# MCU_1.net
KiCad netlist of a schematic drawn in Altium Designer
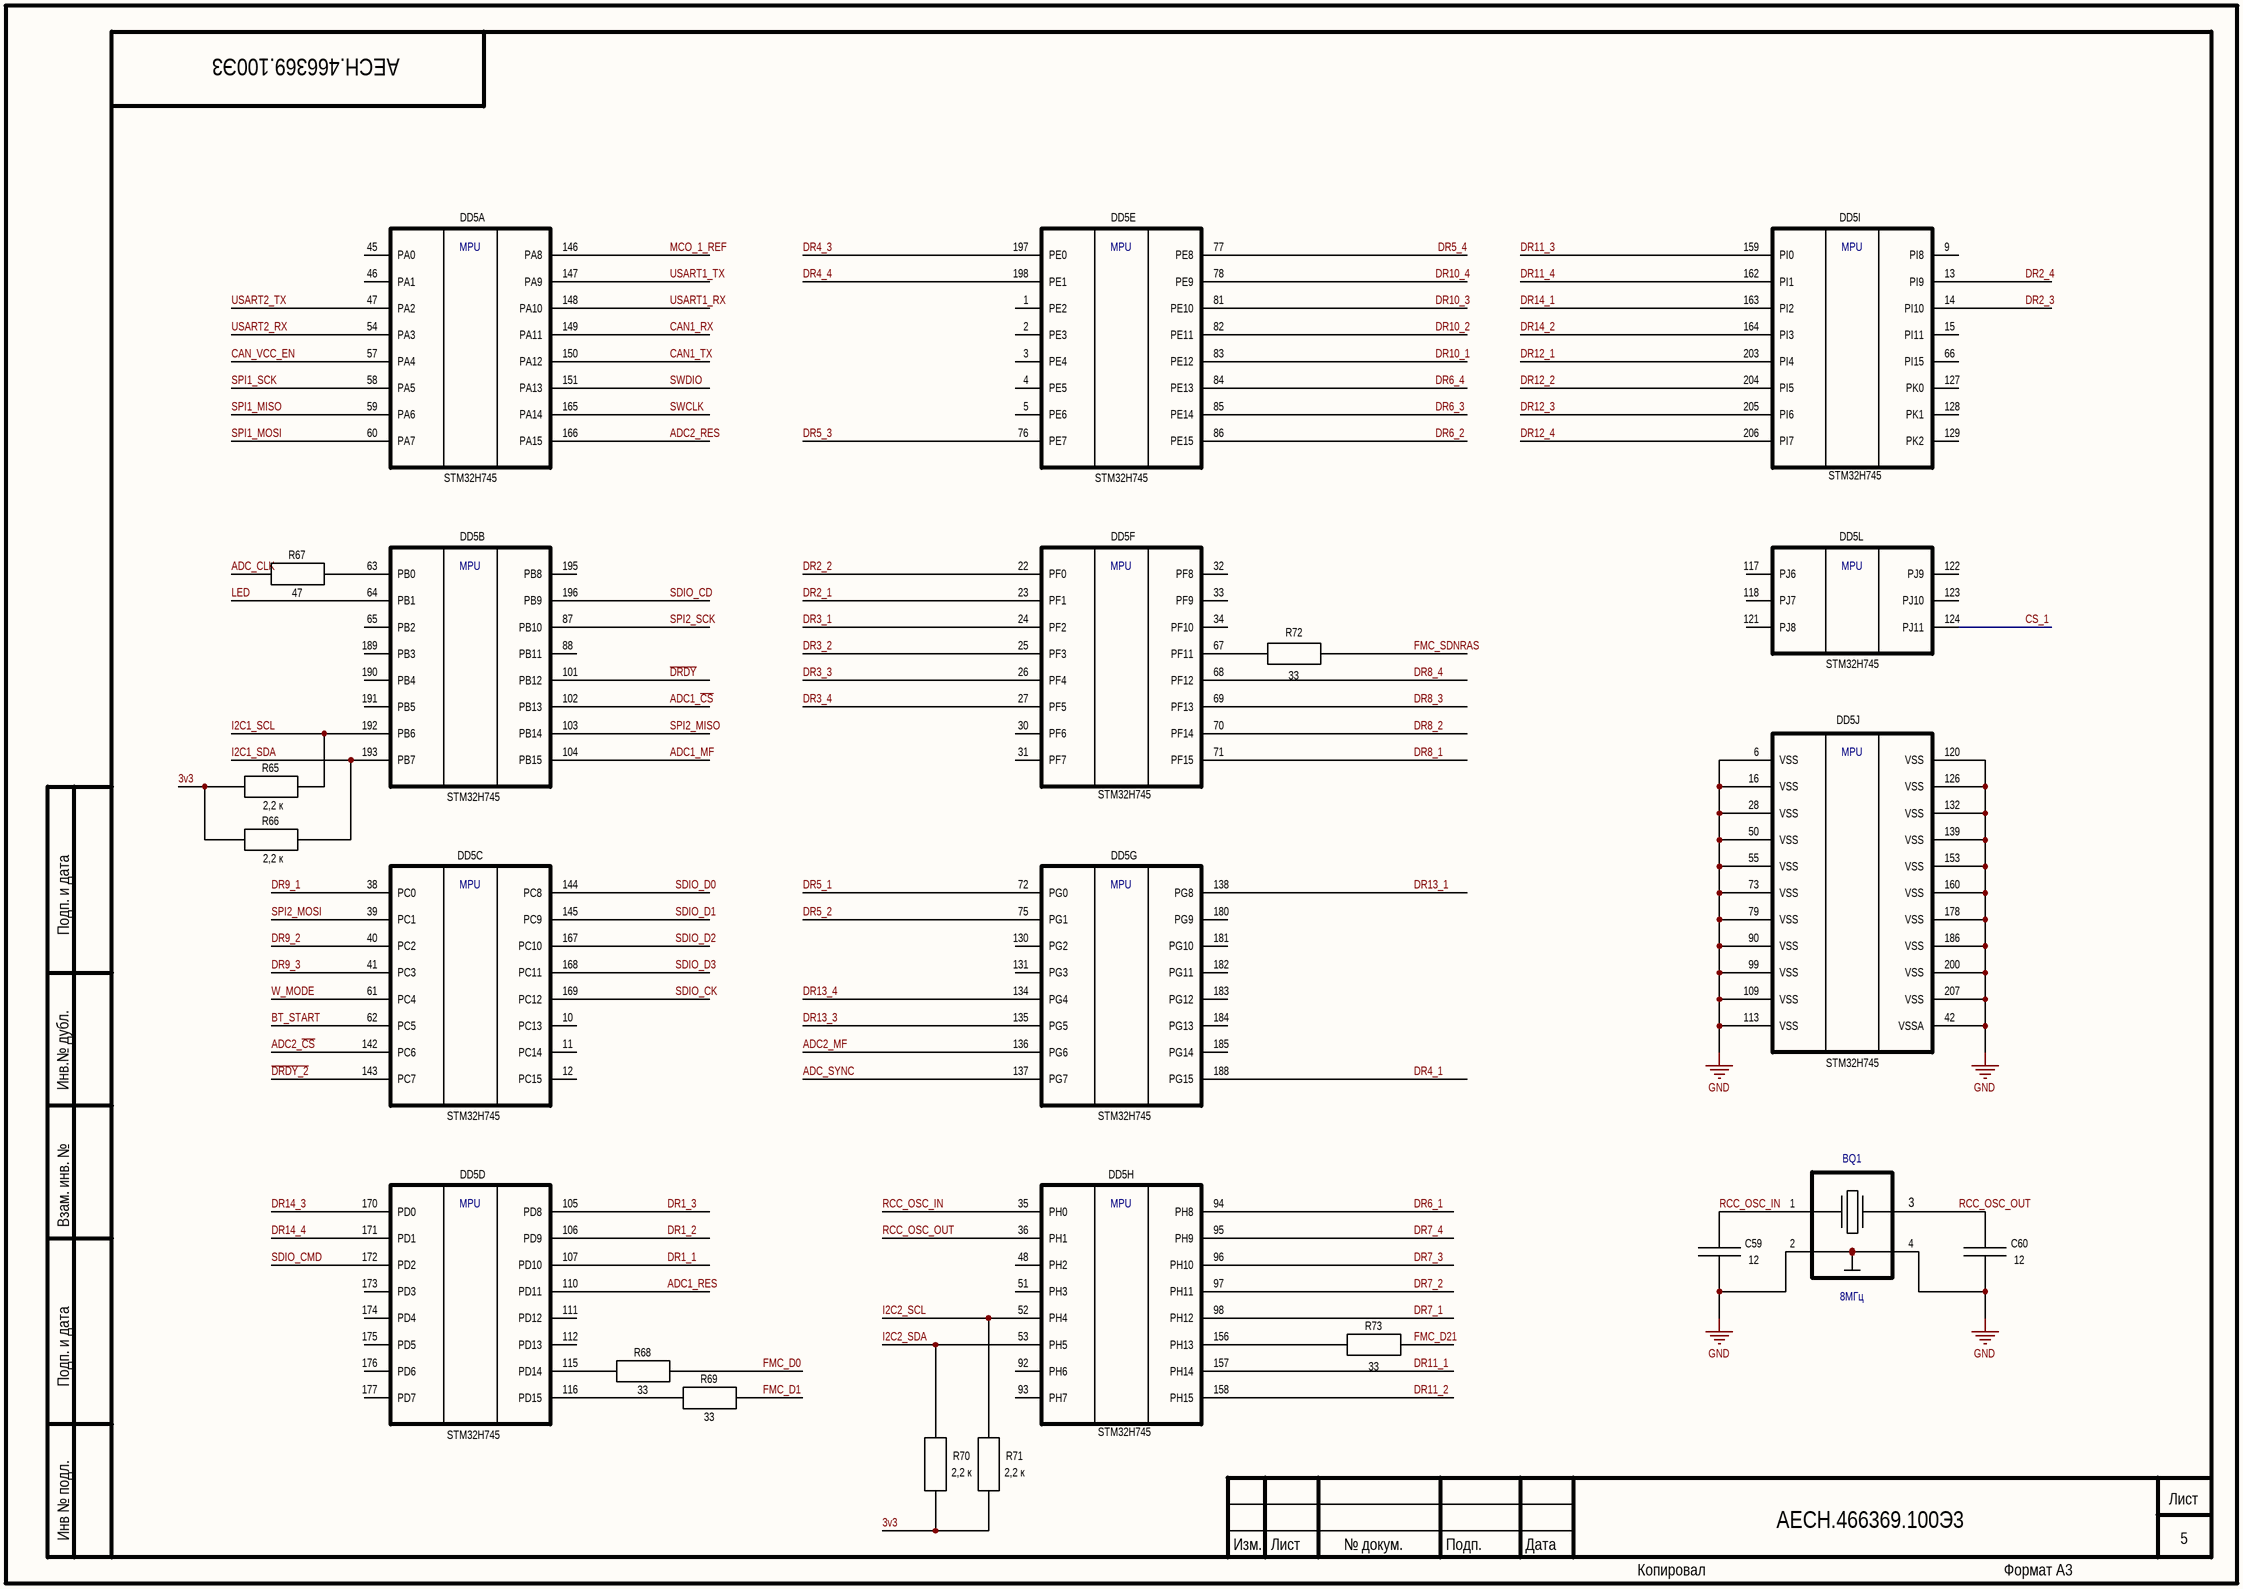
[diagram p0: MCU_1.SchDoc]

(export (version "E")
  (design (tool "Eeschema 10.0.6"))
  (components
    (comp (ref "BQ1")
      (value "8МГц")
      (footprint "Crystal_0532")
      (fields (field (name "PARTNUMBER") "KX-9AT 8.0 MHZ"))
      (libsource (lib "5ko") (part "OSC_4"))
    )
    (comp (ref "C59")
      (value "12")
      (footprint "C0603")
      (fields
        (field (name "TOLERANCE") "±10%")
        (field (name "VOLTAGE") "50 В")
        (field (name "PARTNUMBER") "GRM1885C1H120JA01J")
      )
      (libsource (lib "5ko") (part "C"))
    )
    (comp (ref "C60")
      (value "12")
      (footprint "C0603")
      (fields
        (field (name "TOLERANCE") "±10%")
        (field (name "VOLTAGE") "50 В")
        (field (name "PARTNUMBER") "GRM1885C1H120JA01J")
      )
      (libsource (lib "5ko") (part "C"))
    )
    (comp (ref "DD5") (value "STM32H745") (footprint "LQFP208") (libsource (lib "5ko") (part "STM32H745")))
    (comp (ref "R65")
      (value "2,2 к")
      (footprint "R0603")
      (fields
        (field (name "TOLERANCE") "±5%")
        (field (name "POWER") "0.1 Вт")
        (field (name "PARTNUMBER") "RC0603JR-072K2L")
      )
      (libsource (lib "5ko") (part "R"))
    )
    (comp (ref "R66")
      (value "2,2 к")
      (footprint "R0603")
      (fields
        (field (name "TOLERANCE") "±5%")
        (field (name "POWER") "0.1 Вт")
        (field (name "PARTNUMBER") "RC0603JR-072K2L")
      )
      (libsource (lib "5ko") (part "R"))
    )
    (comp (ref "R67")
      (value "47")
      (footprint "R0603")
      (fields
        (field (name "TOLERANCE") "±5%")
        (field (name "POWER") "0.1 Вт")
        (field (name "PARTNUMBER") "RC0603JR-0747RL")
      )
      (libsource (lib "5ko") (part "R"))
    )
    (comp (ref "R68")
      (value "33")
      (footprint "R0603")
      (fields
        (field (name "TOLERANCE") "±5%")
        (field (name "POWER") "0.1 Вт")
        (field (name "PARTNUMBER") "RC0603JR-0733RL")
      )
      (libsource (lib "5ko") (part "R"))
    )
    (comp (ref "R69")
      (value "33")
      (footprint "R0603")
      (fields
        (field (name "TOLERANCE") "±5%")
        (field (name "POWER") "0.1 Вт")
        (field (name "PARTNUMBER") "RC0603JR-0733RL")
      )
      (libsource (lib "5ko") (part "R"))
    )
    (comp (ref "R70")
      (value "2,2 к")
      (footprint "R0603")
      (fields
        (field (name "TOLERANCE") "±5%")
        (field (name "POWER") "0.1 Вт")
        (field (name "PARTNUMBER") "RC0603JR-072K2L")
      )
      (libsource (lib "5ko") (part "R"))
    )
    (comp (ref "R71")
      (value "2,2 к")
      (footprint "R0603")
      (fields
        (field (name "TOLERANCE") "±5%")
        (field (name "POWER") "0.1 Вт")
        (field (name "PARTNUMBER") "RC0603JR-072K2L")
      )
      (libsource (lib "5ko") (part "R"))
    )
    (comp (ref "R72")
      (value "33")
      (footprint "R0603")
      (fields
        (field (name "TOLERANCE") "±5%")
        (field (name "POWER") "0.1 Вт")
        (field (name "PARTNUMBER") "RC0603JR-0733RL")
      )
      (libsource (lib "5ko") (part "R"))
    )
    (comp (ref "R73")
      (value "33")
      (footprint "R0603")
      (fields
        (field (name "TOLERANCE") "±5%")
        (field (name "POWER") "0.1 Вт")
        (field (name "PARTNUMBER") "RC0603JR-0733RL")
      )
      (libsource (lib "5ko") (part "R"))
    )
  )
  (nets
    (net (code "1") (name "/3v3") (class "Default")
      (node (ref "R65") (pin "2") (pinfunction "2_2") (pintype "passive"))
      (node (ref "R66") (pin "2") (pinfunction "2_2") (pintype "passive"))
      (node (ref "R70") (pin "2") (pinfunction "2_2") (pintype "passive"))
      (node (ref "R71") (pin "2") (pinfunction "2_2") (pintype "passive"))
    )
    (net (code "2") (name "/ADC1_MF") (class "Default")
      (node (ref "DD5") (pin "104") (pinfunction "PB15_104") (pintype "passive"))
    )
    (net (code "3") (name "/ADC1_RES") (class "Default")
      (node (ref "DD5") (pin "110") (pinfunction "PD11_110") (pintype "passive"))
    )
    (net (code "4") (name "/ADC1_~{CS}") (class "Default")
      (node (ref "DD5") (pin "102") (pinfunction "PB13_102") (pintype "passive"))
    )
    (net (code "5") (name "/ADC2_MF") (class "Default")
      (node (ref "DD5") (pin "136") (pinfunction "PG6_136") (pintype "passive"))
    )
    (net (code "6") (name "/ADC2_RES") (class "Default")
      (node (ref "DD5") (pin "166") (pinfunction "PA15_166") (pintype "passive"))
    )
    (net (code "7") (name "/ADC2_~{CS}") (class "Default")
      (node (ref "DD5") (pin "142") (pinfunction "PC6_142") (pintype "passive"))
    )
    (net (code "8") (name "/ADC_CLK") (class "Default")
      (node (ref "R67") (pin "1") (pinfunction "1_1") (pintype "passive"))
    )
    (net (code "9") (name "/ADC_SYNC") (class "Default")
      (node (ref "DD5") (pin "137") (pinfunction "PG7_137") (pintype "passive"))
    )
    (net (code "10") (name "/BT_START") (class "Default")
      (node (ref "DD5") (pin "62") (pinfunction "PC5_62") (pintype "passive"))
    )
    (net (code "11") (name "/CAN1_RX") (class "Default")
      (node (ref "DD5") (pin "149") (pinfunction "PA11_149") (pintype "passive"))
    )
    (net (code "12") (name "/CAN1_TX") (class "Default")
      (node (ref "DD5") (pin "150") (pinfunction "PA12_150") (pintype "passive"))
    )
    (net (code "13") (name "/CAN_VCC_EN") (class "Default")
      (node (ref "DD5") (pin "57") (pinfunction "PA4_57") (pintype "passive"))
    )
    (net (code "14") (name "/CS_1") (class "Default")
      (node (ref "DD5") (pin "124") (pinfunction "PJ11_124") (pintype "passive"))
    )
    (net (code "15") (name "/DR1_1") (class "Default")
      (node (ref "DD5") (pin "107") (pinfunction "PD10_107") (pintype "passive"))
    )
    (net (code "16") (name "/DR1_2") (class "Default")
      (node (ref "DD5") (pin "106") (pinfunction "PD9_106") (pintype "passive"))
    )
    (net (code "17") (name "/DR1_3") (class "Default")
      (node (ref "DD5") (pin "105") (pinfunction "PD8_105") (pintype "passive"))
    )
    (net (code "18") (name "/DR2_1") (class "Default")
      (node (ref "DD5") (pin "23") (pinfunction "PF1_23") (pintype "passive"))
    )
    (net (code "19") (name "/DR2_2") (class "Default")
      (node (ref "DD5") (pin "22") (pinfunction "PF0_22") (pintype "passive"))
    )
    (net (code "20") (name "/DR2_3") (class "Default")
      (node (ref "DD5") (pin "14") (pinfunction "PI10_14") (pintype "passive"))
    )
    (net (code "21") (name "/DR2_4") (class "Default")
      (node (ref "DD5") (pin "13") (pinfunction "PI9_13") (pintype "passive"))
    )
    (net (code "22") (name "/DR3_1") (class "Default")
      (node (ref "DD5") (pin "24") (pinfunction "PF2_24") (pintype "passive"))
    )
    (net (code "23") (name "/DR3_2") (class "Default")
      (node (ref "DD5") (pin "25") (pinfunction "PF3_25") (pintype "passive"))
    )
    (net (code "24") (name "/DR3_3") (class "Default")
      (node (ref "DD5") (pin "26") (pinfunction "PF4_26") (pintype "passive"))
    )
    (net (code "25") (name "/DR3_4") (class "Default")
      (node (ref "DD5") (pin "27") (pinfunction "PF5_27") (pintype "passive"))
    )
    (net (code "26") (name "/DR4_1") (class "Default")
      (node (ref "DD5") (pin "188") (pinfunction "PG15_188") (pintype "passive"))
    )
    (net (code "27") (name "/DR4_3") (class "Default")
      (node (ref "DD5") (pin "197") (pinfunction "PE0_197") (pintype "passive"))
    )
    (net (code "28") (name "/DR4_4") (class "Default")
      (node (ref "DD5") (pin "198") (pinfunction "PE1_198") (pintype "passive"))
    )
    (net (code "29") (name "/DR5_1") (class "Default")
      (node (ref "DD5") (pin "72") (pinfunction "PG0_72") (pintype "passive"))
    )
    (net (code "30") (name "/DR5_2") (class "Default")
      (node (ref "DD5") (pin "75") (pinfunction "PG1_75") (pintype "passive"))
    )
    (net (code "31") (name "/DR5_3") (class "Default")
      (node (ref "DD5") (pin "76") (pinfunction "PE7_76") (pintype "passive"))
    )
    (net (code "32") (name "/DR5_4") (class "Default")
      (node (ref "DD5") (pin "77") (pinfunction "PE8_77") (pintype "passive"))
    )
    (net (code "33") (name "/DR6_1") (class "Default")
      (node (ref "DD5") (pin "94") (pinfunction "PH8_94") (pintype "passive"))
    )
    (net (code "34") (name "/DR6_2") (class "Default")
      (node (ref "DD5") (pin "86") (pinfunction "PE15_86") (pintype "passive"))
    )
    (net (code "35") (name "/DR6_3") (class "Default")
      (node (ref "DD5") (pin "85") (pinfunction "PE14_85") (pintype "passive"))
    )
    (net (code "36") (name "/DR6_4") (class "Default")
      (node (ref "DD5") (pin "84") (pinfunction "PE13_84") (pintype "passive"))
    )
    (net (code "37") (name "/DR7_1") (class "Default")
      (node (ref "DD5") (pin "98") (pinfunction "PH12_98") (pintype "passive"))
    )
    (net (code "38") (name "/DR7_2") (class "Default")
      (node (ref "DD5") (pin "97") (pinfunction "PH11_97") (pintype "passive"))
    )
    (net (code "39") (name "/DR7_3") (class "Default")
      (node (ref "DD5") (pin "96") (pinfunction "PH10_96") (pintype "passive"))
    )
    (net (code "40") (name "/DR7_4") (class "Default")
      (node (ref "DD5") (pin "95") (pinfunction "PH9_95") (pintype "passive"))
    )
    (net (code "41") (name "/DR8_1") (class "Default")
      (node (ref "DD5") (pin "71") (pinfunction "PF15_71") (pintype "passive"))
    )
    (net (code "42") (name "/DR8_2") (class "Default")
      (node (ref "DD5") (pin "70") (pinfunction "PF14_70") (pintype "passive"))
    )
    (net (code "43") (name "/DR8_3") (class "Default")
      (node (ref "DD5") (pin "69") (pinfunction "PF13_69") (pintype "passive"))
    )
    (net (code "44") (name "/DR8_4") (class "Default")
      (node (ref "DD5") (pin "68") (pinfunction "PF12_68") (pintype "passive"))
    )
    (net (code "45") (name "/DR9_1") (class "Default")
      (node (ref "DD5") (pin "38") (pinfunction "PC0_38") (pintype "passive"))
    )
    (net (code "46") (name "/DR9_2") (class "Default")
      (node (ref "DD5") (pin "40") (pinfunction "PC2_40") (pintype "passive"))
    )
    (net (code "47") (name "/DR9_3") (class "Default")
      (node (ref "DD5") (pin "41") (pinfunction "PC3_41") (pintype "passive"))
    )
    (net (code "48") (name "/DR10_1") (class "Default")
      (node (ref "DD5") (pin "83") (pinfunction "PE12_83") (pintype "passive"))
    )
    (net (code "49") (name "/DR10_2") (class "Default")
      (node (ref "DD5") (pin "82") (pinfunction "PE11_82") (pintype "passive"))
    )
    (net (code "50") (name "/DR10_3") (class "Default")
      (node (ref "DD5") (pin "81") (pinfunction "PE10_81") (pintype "passive"))
    )
    (net (code "51") (name "/DR10_4") (class "Default")
      (node (ref "DD5") (pin "78") (pinfunction "PE9_78") (pintype "passive"))
    )
    (net (code "52") (name "/DR11_1") (class "Default")
      (node (ref "DD5") (pin "157") (pinfunction "PH14_157") (pintype "passive"))
    )
    (net (code "53") (name "/DR11_2") (class "Default")
      (node (ref "DD5") (pin "158") (pinfunction "PH15_158") (pintype "passive"))
    )
    (net (code "54") (name "/DR11_3") (class "Default")
      (node (ref "DD5") (pin "159") (pinfunction "PI0_159") (pintype "passive"))
    )
    (net (code "55") (name "/DR11_4") (class "Default")
      (node (ref "DD5") (pin "162") (pinfunction "PI1_162") (pintype "passive"))
    )
    (net (code "56") (name "/DR12_1") (class "Default")
      (node (ref "DD5") (pin "203") (pinfunction "PI4_203") (pintype "passive"))
    )
    (net (code "57") (name "/DR12_2") (class "Default")
      (node (ref "DD5") (pin "204") (pinfunction "PI5_204") (pintype "passive"))
    )
    (net (code "58") (name "/DR12_3") (class "Default")
      (node (ref "DD5") (pin "205") (pinfunction "PI6_205") (pintype "passive"))
    )
    (net (code "59") (name "/DR12_4") (class "Default")
      (node (ref "DD5") (pin "206") (pinfunction "PI7_206") (pintype "passive"))
    )
    (net (code "60") (name "/DR13_1") (class "Default")
      (node (ref "DD5") (pin "138") (pinfunction "PG8_138") (pintype "passive"))
    )
    (net (code "61") (name "/DR13_3") (class "Default")
      (node (ref "DD5") (pin "135") (pinfunction "PG5_135") (pintype "passive"))
    )
    (net (code "62") (name "/DR13_4") (class "Default")
      (node (ref "DD5") (pin "134") (pinfunction "PG4_134") (pintype "passive"))
    )
    (net (code "63") (name "/DR14_1") (class "Default")
      (node (ref "DD5") (pin "163") (pinfunction "PI2_163") (pintype "passive"))
    )
    (net (code "64") (name "/DR14_2") (class "Default")
      (node (ref "DD5") (pin "164") (pinfunction "PI3_164") (pintype "passive"))
    )
    (net (code "65") (name "/DR14_3") (class "Default")
      (node (ref "DD5") (pin "170") (pinfunction "PD0_170") (pintype "passive"))
    )
    (net (code "66") (name "/DR14_4") (class "Default")
      (node (ref "DD5") (pin "171") (pinfunction "PD1_171") (pintype "passive"))
    )
    (net (code "67") (name "/FMC_D0") (class "Default")
      (node (ref "R68") (pin "1") (pinfunction "1_1") (pintype "passive"))
    )
    (net (code "68") (name "/FMC_D1") (class "Default")
      (node (ref "R69") (pin "1") (pinfunction "1_1") (pintype "passive"))
    )
    (net (code "69") (name "/FMC_D21") (class "Default")
      (node (ref "R73") (pin "1") (pinfunction "1_1") (pintype "passive"))
    )
    (net (code "70") (name "/FMC_SDNRAS") (class "Default")
      (node (ref "R72") (pin "1") (pinfunction "1_1") (pintype "passive"))
    )
    (net (code "71") (name "/I2C1_SCL") (class "Default")
      (node (ref "DD5") (pin "192") (pinfunction "PB6_192") (pintype "passive"))
      (node (ref "R65") (pin "1") (pinfunction "1_1") (pintype "passive"))
    )
    (net (code "72") (name "/I2C1_SDA") (class "Default")
      (node (ref "DD5") (pin "193") (pinfunction "PB7_193") (pintype "passive"))
      (node (ref "R66") (pin "1") (pinfunction "1_1") (pintype "passive"))
    )
    (net (code "73") (name "/I2C2_SCL") (class "Default")
      (node (ref "DD5") (pin "52") (pinfunction "PH4_52") (pintype "passive"))
      (node (ref "R71") (pin "1") (pinfunction "1_1") (pintype "passive"))
    )
    (net (code "74") (name "/I2C2_SDA") (class "Default")
      (node (ref "DD5") (pin "53") (pinfunction "PH5_53") (pintype "passive"))
      (node (ref "R70") (pin "1") (pinfunction "1_1") (pintype "passive"))
    )
    (net (code "75") (name "/LED") (class "Default")
      (node (ref "DD5") (pin "64") (pinfunction "PB1_64") (pintype "passive"))
    )
    (net (code "76") (name "/MCO_1_REF") (class "Default")
      (node (ref "DD5") (pin "146") (pinfunction "PA8_146") (pintype "passive"))
    )
    (net (code "77") (name "/RCC_OSC_IN") (class "Default")
      (node (ref "BQ1") (pin "1") (pinfunction "1_1") (pintype "passive"))
      (node (ref "C59") (pin "1") (pinfunction "1_1") (pintype "passive"))
      (node (ref "DD5") (pin "35") (pinfunction "PH0_35") (pintype "passive"))
    )
    (net (code "78") (name "/RCC_OSC_OUT") (class "Default")
      (node (ref "BQ1") (pin "3") (pinfunction "3_3") (pintype "passive"))
      (node (ref "C60") (pin "1") (pinfunction "1_1") (pintype "passive"))
      (node (ref "DD5") (pin "36") (pinfunction "PH1_36") (pintype "passive"))
    )
    (net (code "79") (name "/SDIO_CD") (class "Default")
      (node (ref "DD5") (pin "196") (pinfunction "PB9_196") (pintype "passive"))
    )
    (net (code "80") (name "/SDIO_CK") (class "Default")
      (node (ref "DD5") (pin "169") (pinfunction "PC12_169") (pintype "passive"))
    )
    (net (code "81") (name "/SDIO_CMD") (class "Default")
      (node (ref "DD5") (pin "172") (pinfunction "PD2_172") (pintype "passive"))
    )
    (net (code "82") (name "/SDIO_D0") (class "Default")
      (node (ref "DD5") (pin "144") (pinfunction "PC8_144") (pintype "passive"))
    )
    (net (code "83") (name "/SDIO_D1") (class "Default")
      (node (ref "DD5") (pin "145") (pinfunction "PC9_145") (pintype "passive"))
    )
    (net (code "84") (name "/SDIO_D2") (class "Default")
      (node (ref "DD5") (pin "167") (pinfunction "PC10_167") (pintype "passive"))
    )
    (net (code "85") (name "/SDIO_D3") (class "Default")
      (node (ref "DD5") (pin "168") (pinfunction "PC11_168") (pintype "passive"))
    )
    (net (code "86") (name "/SPI1_MISO") (class "Default")
      (node (ref "DD5") (pin "59") (pinfunction "PA6_59") (pintype "passive"))
    )
    (net (code "87") (name "/SPI1_MOSI") (class "Default")
      (node (ref "DD5") (pin "60") (pinfunction "PA7_60") (pintype "passive"))
    )
    (net (code "88") (name "/SPI1_SCK") (class "Default")
      (node (ref "DD5") (pin "58") (pinfunction "PA5_58") (pintype "passive"))
    )
    (net (code "89") (name "/SPI2_MISO") (class "Default")
      (node (ref "DD5") (pin "103") (pinfunction "PB14_103") (pintype "passive"))
    )
    (net (code "90") (name "/SPI2_MOSI") (class "Default")
      (node (ref "DD5") (pin "39") (pinfunction "PC1_39") (pintype "passive"))
    )
    (net (code "91") (name "/SPI2_SCK") (class "Default")
      (node (ref "DD5") (pin "87") (pinfunction "PB10_87") (pintype "passive"))
    )
    (net (code "92") (name "/SWCLK") (class "Default")
      (node (ref "DD5") (pin "165") (pinfunction "PA14_165") (pintype "passive"))
    )
    (net (code "93") (name "/SWDIO") (class "Default")
      (node (ref "DD5") (pin "151") (pinfunction "PA13_151") (pintype "passive"))
    )
    (net (code "94") (name "/USART1_RX") (class "Default")
      (node (ref "DD5") (pin "148") (pinfunction "PA10_148") (pintype "passive"))
    )
    (net (code "95") (name "/USART1_TX") (class "Default")
      (node (ref "DD5") (pin "147") (pinfunction "PA9_147") (pintype "passive"))
    )
    (net (code "96") (name "/USART2_RX") (class "Default")
      (node (ref "DD5") (pin "54") (pinfunction "PA3_54") (pintype "passive"))
    )
    (net (code "97") (name "/USART2_TX") (class "Default")
      (node (ref "DD5") (pin "47") (pinfunction "PA2_47") (pintype "passive"))
    )
    (net (code "98") (name "/W_MODE") (class "Default")
      (node (ref "DD5") (pin "61") (pinfunction "PC4_61") (pintype "passive"))
    )
    (net (code "99") (name "/~{DRDY_2}") (class "Default")
      (node (ref "DD5") (pin "143") (pinfunction "PC7_143") (pintype "passive"))
    )
    (net (code "100") (name "/~{DRDY}") (class "Default")
      (node (ref "DD5") (pin "101") (pinfunction "PB12_101") (pintype "passive"))
    )
    (net (code "101") (name "GND") (class "Default")
      (node (ref "BQ1") (pin "2") (pinfunction "2_2") (pintype "passive"))
      (node (ref "BQ1") (pin "4") (pinfunction "4_4") (pintype "passive"))
      (node (ref "C59") (pin "2") (pinfunction "2_2") (pintype "passive"))
      (node (ref "C60") (pin "2") (pinfunction "2_2") (pintype "passive"))
      (node (ref "DD5") (pin "109") (pinfunction "VSS_109") (pintype "passive"))
      (node (ref "DD5") (pin "113") (pinfunction "VSS_113") (pintype "passive"))
      (node (ref "DD5") (pin "120") (pinfunction "VSS_120") (pintype "passive"))
      (node (ref "DD5") (pin "126") (pinfunction "VSS_126") (pintype "passive"))
      (node (ref "DD5") (pin "132") (pinfunction "VSS_132") (pintype "passive"))
      (node (ref "DD5") (pin "139") (pinfunction "VSS_139") (pintype "passive"))
      (node (ref "DD5") (pin "153") (pinfunction "VSS_153") (pintype "passive"))
      (node (ref "DD5") (pin "16") (pinfunction "VSS_16") (pintype "passive"))
      (node (ref "DD5") (pin "160") (pinfunction "VSS_160") (pintype "passive"))
      (node (ref "DD5") (pin "178") (pinfunction "VSS_178") (pintype "passive"))
      (node (ref "DD5") (pin "186") (pinfunction "VSS_186") (pintype "passive"))
      (node (ref "DD5") (pin "200") (pinfunction "VSS_200") (pintype "passive"))
      (node (ref "DD5") (pin "207") (pinfunction "VSS_207") (pintype "passive"))
      (node (ref "DD5") (pin "28") (pinfunction "VSS_28") (pintype "passive"))
      (node (ref "DD5") (pin "42") (pinfunction "VSSA_42") (pintype "passive"))
      (node (ref "DD5") (pin "50") (pinfunction "VSS_50") (pintype "passive"))
      (node (ref "DD5") (pin "55") (pinfunction "VSS_55") (pintype "passive"))
      (node (ref "DD5") (pin "6") (pinfunction "VSS_6") (pintype "passive"))
      (node (ref "DD5") (pin "73") (pinfunction "VSS_73") (pintype "passive"))
      (node (ref "DD5") (pin "79") (pinfunction "VSS_79") (pintype "passive"))
      (node (ref "DD5") (pin "90") (pinfunction "VSS_90") (pintype "passive"))
      (node (ref "DD5") (pin "99") (pinfunction "VSS_99") (pintype "passive"))
    )
    (net (code "102") (name "Net-(DD5B-PB0)") (class "Default")
      (node (ref "DD5") (pin "63") (pinfunction "PB0_63") (pintype "passive"))
      (node (ref "R67") (pin "2") (pinfunction "2_2") (pintype "passive"))
    )
    (net (code "103") (name "Net-(DD5D-PD14)") (class "Default")
      (node (ref "DD5") (pin "115") (pinfunction "PD14_115") (pintype "passive"))
      (node (ref "R68") (pin "2") (pinfunction "2_2") (pintype "passive"))
    )
    (net (code "104") (name "Net-(DD5D-PD15)") (class "Default")
      (node (ref "DD5") (pin "116") (pinfunction "PD15_116") (pintype "passive"))
      (node (ref "R69") (pin "2") (pinfunction "2_2") (pintype "passive"))
    )
    (net (code "105") (name "Net-(DD5F-PF11)") (class "Default")
      (node (ref "DD5") (pin "67") (pinfunction "PF11_67") (pintype "passive"))
      (node (ref "R72") (pin "2") (pinfunction "2_2") (pintype "passive"))
    )
    (net (code "106") (name "Net-(DD5H-PH13)") (class "Default")
      (node (ref "DD5") (pin "156") (pinfunction "PH13_156") (pintype "passive"))
      (node (ref "R73") (pin "2") (pinfunction "2_2") (pintype "passive"))
    )
    (net (code "107") (name "unconnected-(DD5A-PA0-Pad45)") (class "Default")
      (node (ref "DD5") (pin "45") (pinfunction "PA0_45") (pintype "passive"))
    )
    (net (code "108") (name "unconnected-(DD5A-PA1-Pad46)") (class "Default")
      (node (ref "DD5") (pin "46") (pinfunction "PA1_46") (pintype "passive"))
    )
    (net (code "109") (name "unconnected-(DD5B-PB2-Pad65)") (class "Default")
      (node (ref "DD5") (pin "65") (pinfunction "PB2_65") (pintype "passive"))
    )
    (net (code "110") (name "unconnected-(DD5B-PB3-Pad189)") (class "Default")
      (node (ref "DD5") (pin "189") (pinfunction "PB3_189") (pintype "passive"))
    )
    (net (code "111") (name "unconnected-(DD5B-PB4-Pad190)") (class "Default")
      (node (ref "DD5") (pin "190") (pinfunction "PB4_190") (pintype "passive"))
    )
    (net (code "112") (name "unconnected-(DD5B-PB5-Pad191)") (class "Default")
      (node (ref "DD5") (pin "191") (pinfunction "PB5_191") (pintype "passive"))
    )
    (net (code "113") (name "unconnected-(DD5B-PB8-Pad195)") (class "Default")
      (node (ref "DD5") (pin "195") (pinfunction "PB8_195") (pintype "passive"))
    )
    (net (code "114") (name "unconnected-(DD5B-PB11-Pad88)") (class "Default")
      (node (ref "DD5") (pin "88") (pinfunction "PB11_88") (pintype "passive"))
    )
    (net (code "115") (name "unconnected-(DD5C-PC13-Pad10)") (class "Default")
      (node (ref "DD5") (pin "10") (pinfunction "PC13_10") (pintype "passive"))
    )
    (net (code "116") (name "unconnected-(DD5C-PC14-Pad11)") (class "Default")
      (node (ref "DD5") (pin "11") (pinfunction "PC14_11") (pintype "passive"))
    )
    (net (code "117") (name "unconnected-(DD5C-PC15-Pad12)") (class "Default")
      (node (ref "DD5") (pin "12") (pinfunction "PC15_12") (pintype "passive"))
    )
    (net (code "118") (name "unconnected-(DD5D-PD3-Pad173)") (class "Default")
      (node (ref "DD5") (pin "173") (pinfunction "PD3_173") (pintype "passive"))
    )
    (net (code "119") (name "unconnected-(DD5D-PD4-Pad174)") (class "Default")
      (node (ref "DD5") (pin "174") (pinfunction "PD4_174") (pintype "passive"))
    )
    (net (code "120") (name "unconnected-(DD5D-PD5-Pad175)") (class "Default")
      (node (ref "DD5") (pin "175") (pinfunction "PD5_175") (pintype "passive"))
    )
    (net (code "121") (name "unconnected-(DD5D-PD6-Pad176)") (class "Default")
      (node (ref "DD5") (pin "176") (pinfunction "PD6_176") (pintype "passive"))
    )
    (net (code "122") (name "unconnected-(DD5D-PD7-Pad177)") (class "Default")
      (node (ref "DD5") (pin "177") (pinfunction "PD7_177") (pintype "passive"))
    )
    (net (code "123") (name "unconnected-(DD5D-PD12-Pad111)") (class "Default")
      (node (ref "DD5") (pin "111") (pinfunction "PD12_111") (pintype "passive"))
    )
    (net (code "124") (name "unconnected-(DD5D-PD13-Pad112)") (class "Default")
      (node (ref "DD5") (pin "112") (pinfunction "PD13_112") (pintype "passive"))
    )
    (net (code "125") (name "unconnected-(DD5E-PE2-Pad1)") (class "Default")
      (node (ref "DD5") (pin "1") (pinfunction "PE2_1") (pintype "passive"))
    )
    (net (code "126") (name "unconnected-(DD5E-PE3-Pad2)") (class "Default")
      (node (ref "DD5") (pin "2") (pinfunction "PE3_2") (pintype "passive"))
    )
    (net (code "127") (name "unconnected-(DD5E-PE4-Pad3)") (class "Default")
      (node (ref "DD5") (pin "3") (pinfunction "PE4_3") (pintype "passive"))
    )
    (net (code "128") (name "unconnected-(DD5E-PE5-Pad4)") (class "Default")
      (node (ref "DD5") (pin "4") (pinfunction "PE5_4") (pintype "passive"))
    )
    (net (code "129") (name "unconnected-(DD5E-PE6-Pad5)") (class "Default")
      (node (ref "DD5") (pin "5") (pinfunction "PE6_5") (pintype "passive"))
    )
    (net (code "130") (name "unconnected-(DD5F-PF6-Pad30)") (class "Default")
      (node (ref "DD5") (pin "30") (pinfunction "PF6_30") (pintype "passive"))
    )
    (net (code "131") (name "unconnected-(DD5F-PF7-Pad31)") (class "Default")
      (node (ref "DD5") (pin "31") (pinfunction "PF7_31") (pintype "passive"))
    )
    (net (code "132") (name "unconnected-(DD5F-PF8-Pad32)") (class "Default")
      (node (ref "DD5") (pin "32") (pinfunction "PF8_32") (pintype "passive"))
    )
    (net (code "133") (name "unconnected-(DD5F-PF9-Pad33)") (class "Default")
      (node (ref "DD5") (pin "33") (pinfunction "PF9_33") (pintype "passive"))
    )
    (net (code "134") (name "unconnected-(DD5F-PF10-Pad34)") (class "Default")
      (node (ref "DD5") (pin "34") (pinfunction "PF10_34") (pintype "passive"))
    )
    (net (code "135") (name "unconnected-(DD5G-PG2-Pad130)") (class "Default")
      (node (ref "DD5") (pin "130") (pinfunction "PG2_130") (pintype "passive"))
    )
    (net (code "136") (name "unconnected-(DD5G-PG3-Pad131)") (class "Default")
      (node (ref "DD5") (pin "131") (pinfunction "PG3_131") (pintype "passive"))
    )
    (net (code "137") (name "unconnected-(DD5G-PG9-Pad180)") (class "Default")
      (node (ref "DD5") (pin "180") (pinfunction "PG9_180") (pintype "passive"))
    )
    (net (code "138") (name "unconnected-(DD5G-PG10-Pad181)") (class "Default")
      (node (ref "DD5") (pin "181") (pinfunction "PG10_181") (pintype "passive"))
    )
    (net (code "139") (name "unconnected-(DD5G-PG11-Pad182)") (class "Default")
      (node (ref "DD5") (pin "182") (pinfunction "PG11_182") (pintype "passive"))
    )
    (net (code "140") (name "unconnected-(DD5G-PG12-Pad183)") (class "Default")
      (node (ref "DD5") (pin "183") (pinfunction "PG12_183") (pintype "passive"))
    )
    (net (code "141") (name "unconnected-(DD5G-PG13-Pad184)") (class "Default")
      (node (ref "DD5") (pin "184") (pinfunction "PG13_184") (pintype "passive"))
    )
    (net (code "142") (name "unconnected-(DD5G-PG14-Pad185)") (class "Default")
      (node (ref "DD5") (pin "185") (pinfunction "PG14_185") (pintype "passive"))
    )
    (net (code "143") (name "unconnected-(DD5H-PH2-Pad48)") (class "Default")
      (node (ref "DD5") (pin "48") (pinfunction "PH2_48") (pintype "passive"))
    )
    (net (code "144") (name "unconnected-(DD5H-PH3-Pad51)") (class "Default")
      (node (ref "DD5") (pin "51") (pinfunction "PH3_51") (pintype "passive"))
    )
    (net (code "145") (name "unconnected-(DD5H-PH6-Pad92)") (class "Default")
      (node (ref "DD5") (pin "92") (pinfunction "PH6_92") (pintype "passive"))
    )
    (net (code "146") (name "unconnected-(DD5H-PH7-Pad93)") (class "Default")
      (node (ref "DD5") (pin "93") (pinfunction "PH7_93") (pintype "passive"))
    )
    (net (code "147") (name "unconnected-(DD5I-PI8-Pad9)") (class "Default")
      (node (ref "DD5") (pin "9") (pinfunction "PI8_9") (pintype "passive"))
    )
    (net (code "148") (name "unconnected-(DD5I-PI11-Pad15)") (class "Default")
      (node (ref "DD5") (pin "15") (pinfunction "PI11_15") (pintype "passive"))
    )
    (net (code "149") (name "unconnected-(DD5I-PI15-Pad66)") (class "Default")
      (node (ref "DD5") (pin "66") (pinfunction "PI15_66") (pintype "passive"))
    )
    (net (code "150") (name "unconnected-(DD5I-PK0-Pad127)") (class "Default")
      (node (ref "DD5") (pin "127") (pinfunction "PK0_127") (pintype "passive"))
    )
    (net (code "151") (name "unconnected-(DD5I-PK1-Pad128)") (class "Default")
      (node (ref "DD5") (pin "128") (pinfunction "PK1_128") (pintype "passive"))
    )
    (net (code "152") (name "unconnected-(DD5I-PK2-Pad129)") (class "Default")
      (node (ref "DD5") (pin "129") (pinfunction "PK2_129") (pintype "passive"))
    )
    (net (code "153") (name "unconnected-(DD5L-PJ6-Pad117)") (class "Default")
      (node (ref "DD5") (pin "117") (pinfunction "PJ6_117") (pintype "passive"))
    )
    (net (code "154") (name "unconnected-(DD5L-PJ7-Pad118)") (class "Default")
      (node (ref "DD5") (pin "118") (pinfunction "PJ7_118") (pintype "passive"))
    )
    (net (code "155") (name "unconnected-(DD5L-PJ8-Pad121)") (class "Default")
      (node (ref "DD5") (pin "121") (pinfunction "PJ8_121") (pintype "passive"))
    )
    (net (code "156") (name "unconnected-(DD5L-PJ9-Pad122)") (class "Default")
      (node (ref "DD5") (pin "122") (pinfunction "PJ9_122") (pintype "passive"))
    )
    (net (code "157") (name "unconnected-(DD5L-PJ10-Pad123)") (class "Default")
      (node (ref "DD5") (pin "123") (pinfunction "PJ10_123") (pintype "passive"))
    )
  )
)
